# B502DA.net
KiCad netlist of a schematic drawn in Altium Designer
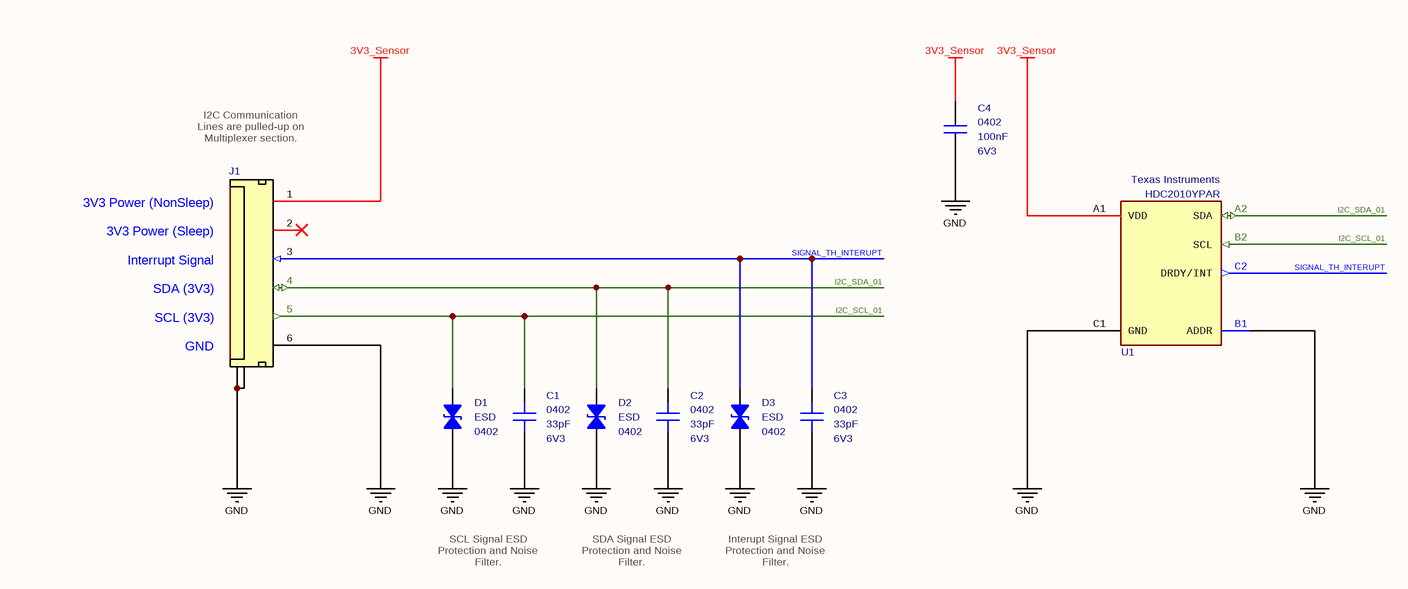
[diagram p0: B502DA.SchDoc]

(export (version "E")
  (design (tool "Eeschema 10.0.6"))
  (components
    (comp (ref "C1")
      (value "33pF")
      (footprint "CAPACITOR_0402")
      (description "Capacitor - 33pF [0402] (Ceramic)")
      (fields
        (field (name "MANUFACTURER_PART_NUMBER") "C0402C330J9RACAUTO")
        (field (name "MOUSER_PART_NUMBER") "80-C0402C330J9RAUTO")
        (field (name "CASE") "0402")
        (field (name "VOLTAGE") "6V3")
      )
      (libsource (lib "Ovoo_Schematic") (part "Capacitor - 33pF [0402-6V3]"))
    )
    (comp (ref "C2")
      (value "33pF")
      (footprint "CAPACITOR_0402")
      (description "Capacitor - 33pF [0402] (Ceramic)")
      (fields
        (field (name "MANUFACTURER_PART_NUMBER") "C0402C330J9RACAUTO")
        (field (name "MOUSER_PART_NUMBER") "80-C0402C330J9RAUTO")
        (field (name "CASE") "0402")
        (field (name "VOLTAGE") "6V3")
      )
      (libsource (lib "Ovoo_Schematic") (part "Capacitor - 33pF [0402-6V3]"))
    )
    (comp (ref "C3")
      (value "33pF")
      (footprint "CAPACITOR_0402")
      (description "Capacitor - 33pF [0402] (Ceramic)")
      (fields
        (field (name "MANUFACTURER_PART_NUMBER") "C0402C330J9RACAUTO")
        (field (name "MOUSER_PART_NUMBER") "80-C0402C330J9RAUTO")
        (field (name "CASE") "0402")
        (field (name "VOLTAGE") "6V3")
      )
      (libsource (lib "Ovoo_Schematic") (part "Capacitor - 33pF [0402-6V3]"))
    )
    (comp (ref "C4")
      (value "100nF")
      (footprint "CAPACITOR_0402")
      (description "Capacitor - 100nF [0402-6V3] (Ceramic)")
      (fields
        (field (name "MANUFACTURER_PART_NUMBER") "04026D104KAT4A")
        (field (name "MOUSER_PART_NUMBER") "581-04026D104KAT4A")
        (field (name "CASE") "0402")
        (field (name "VOLTAGE") "6V3")
      )
      (libsource (lib "Ovoo_Schematic") (part "Capacitor - 100nF [0402-6V3]"))
    )
    (comp (ref "D1")
      (value "ESD Suppressors")
      (footprint "ESD_0402")
      (description "TVS Diode (Bi-directional)")
      (fields
        (field (name "MANUFACTURER_PART_NUMBER") "0402ESDA-MLP1")
        (field (name "MOUSER_PART_NUMBER") "504-0402ESDA-MLP1")
        (field (name "CASE") "0402")
      )
      (libsource (lib "Ovoo_Schematic") (part "Diode - ESD Protection"))
    )
    (comp (ref "D2")
      (value "ESD Suppressors")
      (footprint "ESD_0402")
      (description "TVS Diode (Bi-directional)")
      (fields
        (field (name "MANUFACTURER_PART_NUMBER") "0402ESDA-MLP1")
        (field (name "MOUSER_PART_NUMBER") "504-0402ESDA-MLP1")
        (field (name "CASE") "0402")
      )
      (libsource (lib "Ovoo_Schematic") (part "Diode - ESD Protection"))
    )
    (comp (ref "D3")
      (value "ESD Suppressors")
      (footprint "ESD_0402")
      (description "TVS Diode (Bi-directional)")
      (fields
        (field (name "MANUFACTURER_PART_NUMBER") "0402ESDA-MLP1")
        (field (name "MOUSER_PART_NUMBER") "504-0402ESDA-MLP1")
        (field (name "CASE") "0402")
      )
      (libsource (lib "Ovoo_Schematic") (part "Diode - ESD Protection"))
    )
    (comp (ref "J1")
      (value "T/H Sensor Socket")
      (footprint "Connector_Tunic 6P - H")
      (description "Mini Tunic Connector with 6P")
      (fields (field (name "MANUFACTURER_PART_NUMBER") "53261-0671"))
      (libsource (lib "Ovoo_Schematic") (part "Connector - Mini Tunic 6P (1.25)"))
    )
    (comp (ref "U1")
      (value "Humidity and temperature digital sensor")
      (footprint "HDC2010")
      (fields
        (field (name "MOUSER_PART_NUMBER") "595-HDC2010YPAR")
        (field (name "MANUFACTURER_PART_NUMBER") "HDC2010YPAR")
        (field (name "MANUFACTURER_NAME") "Texas Instruments")
      )
      (libsource (lib "Ovoo_Schematic") (part "IC - HDC2010YPAR"))
    )
  )
  (nets
    (net (code "1") (name "/I2C_SCL_01") (class "Default")
      (node (ref "C1") (pin "2") (pinfunction "2_2") (pintype "passive"))
      (node (ref "D1") (pin "2") (pinfunction "2_2") (pintype "passive"))
      (node (ref "J1") (pin "5") (pinfunction "I2C_SCL_01_5") (pintype "output"))
      (node (ref "U1") (pin "B2") (pinfunction "SCL_B2") (pintype "input"))
    )
    (net (code "2") (name "/I2C_SDA_01") (class "Default")
      (node (ref "C2") (pin "2") (pinfunction "2_2") (pintype "passive"))
      (node (ref "D2") (pin "2") (pinfunction "2_2") (pintype "passive"))
      (node (ref "J1") (pin "4") (pinfunction "I2C_SDA_01_4") (pintype "bidirectional"))
      (node (ref "U1") (pin "A2") (pinfunction "SDA_A2") (pintype "bidirectional"))
    )
    (net (code "3") (name "/SIGNAL_TH_INTERUPT") (class "Default")
      (node (ref "C3") (pin "2") (pinfunction "2_2") (pintype "passive"))
      (node (ref "D3") (pin "2") (pinfunction "2_2") (pintype "passive"))
      (node (ref "J1") (pin "3") (pinfunction "SIGNAL_TH_INTERUPT_3") (pintype "input"))
      (node (ref "U1") (pin "C2") (pinfunction "DRDY/INT_C2") (pintype "output"))
    )
    (net (code "4") (name "3V3_Sensor") (class "Default")
      (node (ref "C4") (pin "1") (pinfunction "1_1") (pintype "passive"))
      (node (ref "J1") (pin "1") (pinfunction "3V3_Sensor_1") (pintype "power_in"))
      (node (ref "U1") (pin "A1") (pinfunction "VDD_A1") (pintype "power_in"))
    )
    (net (code "5") (name "GND") (class "Default")
      (node (ref "C1") (pin "1") (pinfunction "1_1") (pintype "passive"))
      (node (ref "C2") (pin "1") (pinfunction "1_1") (pintype "passive"))
      (node (ref "C3") (pin "1") (pinfunction "1_1") (pintype "passive"))
      (node (ref "C4") (pin "2") (pinfunction "2_2") (pintype "passive"))
      (node (ref "D1") (pin "1") (pinfunction "1_1") (pintype "passive"))
      (node (ref "D2") (pin "1") (pinfunction "1_1") (pintype "passive"))
      (node (ref "D3") (pin "1") (pinfunction "1_1") (pintype "passive"))
      (node (ref "J1") (pin "6") (pinfunction "GND_6") (pintype "power_in"))
      (node (ref "J1") (pin "7") (pinfunction "Termination_7") (pintype "power_in"))
      (node (ref "J1") (pin "8") (pinfunction "Termination_8") (pintype "power_in"))
      (node (ref "U1") (pin "B1") (pinfunction "ADDR_B1") (pintype "passive"))
      (node (ref "U1") (pin "C1") (pinfunction "GND_C1") (pintype "power_in"))
    )
    (net (code "6") (name "unconnected-(J1-3V3_Digital-Pad2)") (class "Default")
      (node (ref "J1") (pin "2") (pinfunction "3V3_Digital_2") (pintype "power_in+no_connect"))
    )
  )
)
